# rs232.net
KiCad netlist of a schematic drawn in Altium Designer
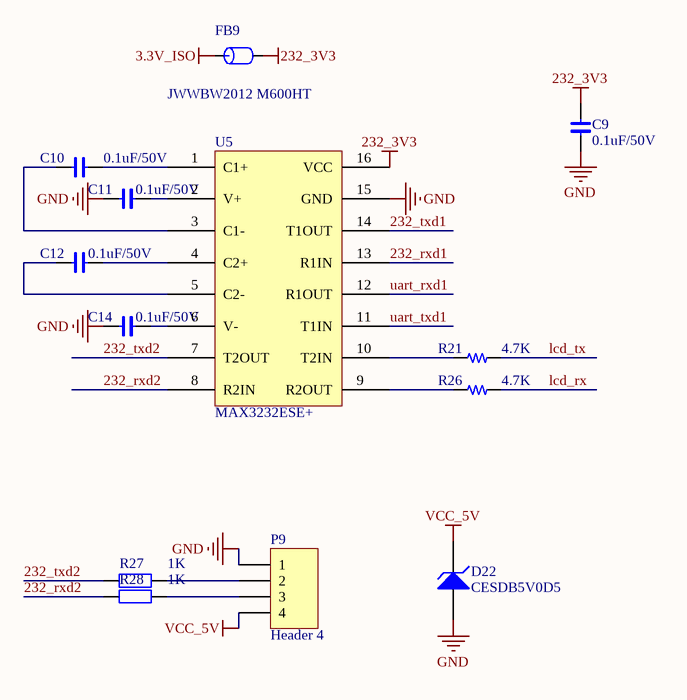
[diagram p0: rs232.SchDoc]

(export (version "E")
  (design (tool "Eeschema 10.0.6"))
  (components
    (comp (ref "C9")
      (value "0.1uF/50V")
      (footprint "0603C")
      (fields (field (name "Comment") "0.1uF"))
      (libsource (lib "Schlib_20110825") (part "C"))
    )
    (comp (ref "C10")
      (value "0.1uF/50V")
      (footprint "0603C")
      (fields (field (name "Comment") "0.1uF"))
      (libsource (lib "Schlib_20110825") (part "C"))
    )
    (comp (ref "C11")
      (value "0.1uF/50V")
      (footprint "0603C")
      (fields (field (name "Comment") "0.1uF"))
      (libsource (lib "Schlib_20110825") (part "C"))
    )
    (comp (ref "C12")
      (value "0.1uF/50V")
      (footprint "0603C")
      (fields (field (name "Comment") "0.1uF"))
      (libsource (lib "Schlib_20110825") (part "C"))
    )
    (comp (ref "C14")
      (value "0.1uF/50V")
      (footprint "0603C")
      (fields (field (name "Comment") "0.1uF"))
      (libsource (lib "Schlib_20110825") (part "C"))
    )
    (comp (ref "D22")
      (value "CESDB5V0D5")
      (footprint "sod323")
      (description "Zener Diode")
      (fields (field (name "PUBLISHER") "Altium Limited"))
      (libsource (lib "Miscellaneous Devices") (part "D Zener"))
    )
    (comp (ref "FB9")
      (value "JWWBW2012 M600HT")
      (footprint "0805R")
      (libsource (lib "Schlib_20110825") (part "FB"))
    )
    (comp (ref "P9")
      (value "Header 4")
      (footprint "2ETYR-5.08-04P-14-100")
      (description "Header, 4-Pin")
      (fields (field (name "PUBLISHER") "Altium Limited"))
      (libsource (lib "Miscellaneous Connectors") (part "Header 4"))
    )
    (comp (ref "R21") (value "4.7K") (footprint "0603R") (libsource (lib "JRJ_1") (part "R")))
    (comp (ref "R26") (value "4.7K") (footprint "0603R") (libsource (lib "JRJ_1") (part "R")))
    (comp (ref "R27") (value "1K") (footprint "0603R") (libsource (lib "MQlibrary") (part "Res0805M")))
    (comp (ref "R28") (value "1K") (footprint "0603R") (libsource (lib "MQlibrary") (part "Res0805M")))
    (comp (ref "U5")
      (value "MAX3232ESE+")
      (footprint "SOIC127P600X265-16N")
      (libsource (lib "Schlib_20110825") (part "MAX3232ESE+"))
    )
  )
  (nets
    (net (code "1") (name "/232_rxd1") (class "Default")
      (node (ref "U5") (pin "13") (pinfunction "R1IN_13") (pintype "passive"))
    )
    (net (code "2") (name "/232_rxd2") (class "Default")
      (node (ref "R28") (pin "1") (pinfunction "1_1") (pintype "passive"))
      (node (ref "U5") (pin "8") (pinfunction "R2IN_8") (pintype "passive"))
    )
    (net (code "3") (name "/232_txd1") (class "Default")
      (node (ref "U5") (pin "14") (pinfunction "T1OUT_14") (pintype "passive"))
    )
    (net (code "4") (name "/232_txd2") (class "Default")
      (node (ref "R27") (pin "1") (pinfunction "1_1") (pintype "passive"))
      (node (ref "U5") (pin "7") (pinfunction "T2OUT_7") (pintype "passive"))
    )
    (net (code "5") (name "/lcd_rx") (class "Default") (node (ref "R26") (pin "2") (pintype "passive")))
    (net (code "6") (name "/lcd_tx") (class "Default") (node (ref "R21") (pin "2") (pintype "passive")))
    (net (code "7") (name "/uart_rxd1") (class "Default")
      (node (ref "U5") (pin "12") (pinfunction "R1OUT_12") (pintype "passive"))
    )
    (net (code "8") (name "/uart_txd1") (class "Default")
      (node (ref "U5") (pin "11") (pinfunction "T1IN_11") (pintype "passive"))
    )
    (net (code "9") (name "3.3V_ISO") (class "Default") (node (ref "FB9") (pin "1") (pintype "passive")))
    (net (code "10") (name "232_3V3") (class "Default")
      (node (ref "C9") (pin "1") (pintype "passive"))
      (node (ref "FB9") (pin "2") (pintype "passive"))
      (node (ref "U5") (pin "16") (pinfunction "VCC_16") (pintype "passive"))
    )
    (net (code "11") (name "GND") (class "Default")
      (node (ref "C11") (pin "2") (pintype "passive"))
      (node (ref "C14") (pin "2") (pintype "passive"))
      (node (ref "C9") (pin "2") (pintype "passive"))
      (node (ref "D22") (pin "1") (pinfunction "A_1") (pintype "passive"))
      (node (ref "P9") (pin "1") (pinfunction "1_1") (pintype "passive"))
      (node (ref "U5") (pin "15") (pinfunction "GND_15") (pintype "passive"))
    )
    (net (code "12") (name "Net-(P9-Pad2)") (class "Default")
      (node (ref "P9") (pin "2") (pinfunction "2_2") (pintype "passive"))
      (node (ref "R27") (pin "2") (pinfunction "2_2") (pintype "passive"))
    )
    (net (code "13") (name "Net-(P9-Pad3)") (class "Default")
      (node (ref "P9") (pin "3") (pinfunction "3_3") (pintype "passive"))
      (node (ref "R28") (pin "2") (pinfunction "2_2") (pintype "passive"))
    )
    (net (code "14") (name "Net-(U5-C1+)") (class "Default")
      (node (ref "C10") (pin "1") (pintype "passive"))
      (node (ref "U5") (pin "1") (pinfunction "C1+_1") (pintype "passive"))
    )
    (net (code "15") (name "Net-(U5-C1-)") (class "Default")
      (node (ref "C10") (pin "2") (pintype "passive"))
      (node (ref "U5") (pin "3") (pinfunction "C1-_3") (pintype "passive"))
    )
    (net (code "16") (name "Net-(U5-C2+)") (class "Default")
      (node (ref "C12") (pin "1") (pintype "passive"))
      (node (ref "U5") (pin "4") (pinfunction "C2+_4") (pintype "passive"))
    )
    (net (code "17") (name "Net-(U5-C2-)") (class "Default")
      (node (ref "C12") (pin "2") (pintype "passive"))
      (node (ref "U5") (pin "5") (pinfunction "C2-_5") (pintype "passive"))
    )
    (net (code "18") (name "Net-(U5-R2OUT)") (class "Default")
      (node (ref "R26") (pin "1") (pintype "passive"))
      (node (ref "U5") (pin "9") (pinfunction "R2OUT_9") (pintype "passive"))
    )
    (net (code "19") (name "Net-(U5-T2IN)") (class "Default")
      (node (ref "R21") (pin "1") (pintype "passive"))
      (node (ref "U5") (pin "10") (pinfunction "T2IN_10") (pintype "passive"))
    )
    (net (code "20") (name "Net-(U5-V+)") (class "Default")
      (node (ref "C11") (pin "1") (pintype "passive"))
      (node (ref "U5") (pin "2") (pinfunction "V+_2") (pintype "passive"))
    )
    (net (code "21") (name "Net-(U5-V-)") (class "Default")
      (node (ref "C14") (pin "1") (pintype "passive"))
      (node (ref "U5") (pin "6") (pinfunction "V-_6") (pintype "passive"))
    )
    (net (code "22") (name "VCC_5V") (class "Default")
      (node (ref "D22") (pin "2") (pinfunction "K_2") (pintype "passive"))
      (node (ref "P9") (pin "4") (pinfunction "4_4") (pintype "passive"))
    )
  )
)
